# Led_Circle.net
KiCad netlist of a schematic drawn in EAGLE
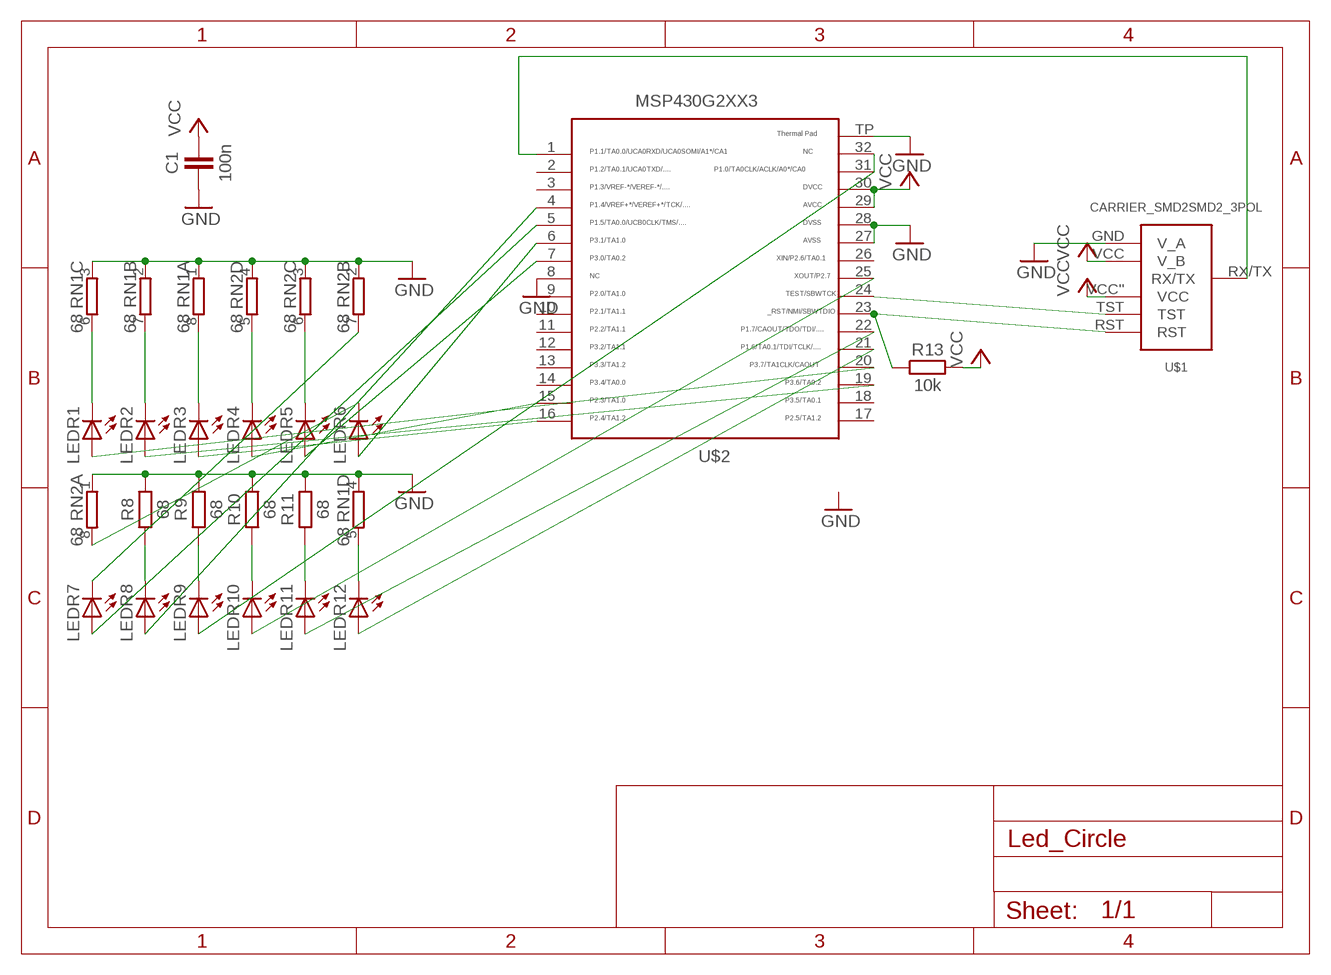
[diagram p0: schematic, sheet 1]

(export (version "E")
  (design (tool "Eeschema 10.0.6"))
  (components
    (comp (ref "C1")
      (value "100n")
      (footprint "eagle-import:603")
      (libsource (lib "eagle-import") (part "CAPACITOR"))
    )
    (comp (ref "LEDR1")
      (value "LEDCHIPLED_0603")
      (footprint "eagle-import:CHIPLED_0603")
      (libsource (lib "eagle-import") (part "LEDCHIPLED_0603"))
    )
    (comp (ref "LEDR2")
      (value "LEDCHIPLED_0603")
      (footprint "eagle-import:CHIPLED_0603")
      (libsource (lib "eagle-import") (part "LEDCHIPLED_0603"))
    )
    (comp (ref "LEDR3")
      (value "LEDCHIPLED_0603")
      (footprint "eagle-import:CHIPLED_0603")
      (libsource (lib "eagle-import") (part "LEDCHIPLED_0603"))
    )
    (comp (ref "LEDR4")
      (value "LEDCHIPLED_0603")
      (footprint "eagle-import:CHIPLED_0603")
      (libsource (lib "eagle-import") (part "LEDCHIPLED_0603"))
    )
    (comp (ref "LEDR5")
      (value "LEDCHIPLED_0603")
      (footprint "eagle-import:CHIPLED_0603")
      (libsource (lib "eagle-import") (part "LEDCHIPLED_0603"))
    )
    (comp (ref "LEDR6")
      (value "LEDCHIPLED_0603")
      (footprint "eagle-import:CHIPLED_0603")
      (libsource (lib "eagle-import") (part "LEDCHIPLED_0603"))
    )
    (comp (ref "LEDR7")
      (value "LEDCHIPLED_0603")
      (footprint "eagle-import:CHIPLED_0603")
      (libsource (lib "eagle-import") (part "LEDCHIPLED_0603"))
    )
    (comp (ref "LEDR8")
      (value "LEDCHIPLED_0603")
      (footprint "eagle-import:CHIPLED_0603")
      (libsource (lib "eagle-import") (part "LEDCHIPLED_0603"))
    )
    (comp (ref "LEDR9")
      (value "LEDCHIPLED_0603")
      (footprint "eagle-import:CHIPLED_0603")
      (libsource (lib "eagle-import") (part "LEDCHIPLED_0603"))
    )
    (comp (ref "LEDR10")
      (value "LEDCHIPLED_0603")
      (footprint "eagle-import:CHIPLED_0603")
      (libsource (lib "eagle-import") (part "LEDCHIPLED_0603"))
    )
    (comp (ref "LEDR11")
      (value "LEDCHIPLED_0603")
      (footprint "eagle-import:CHIPLED_0603")
      (libsource (lib "eagle-import") (part "LEDCHIPLED_0603"))
    )
    (comp (ref "LEDR12")
      (value "LEDCHIPLED_0603")
      (footprint "eagle-import:CHIPLED_0603")
      (libsource (lib "eagle-import") (part "LEDCHIPLED_0603"))
    )
    (comp (ref "R8")
      (value "68")
      (footprint "eagle-import:603")
      (libsource (lib "eagle-import") (part "RESISTOR0603"))
    )
    (comp (ref "R9")
      (value "68")
      (footprint "eagle-import:603")
      (libsource (lib "eagle-import") (part "RESISTOR0603"))
    )
    (comp (ref "R10")
      (value "68")
      (footprint "eagle-import:603")
      (libsource (lib "eagle-import") (part "RESISTOR0603"))
    )
    (comp (ref "R11")
      (value "68")
      (footprint "eagle-import:603")
      (libsource (lib "eagle-import") (part "RESISTOR0603"))
    )
    (comp (ref "R13")
      (value "10k")
      (footprint "eagle-import:603")
      (libsource (lib "eagle-import") (part "RESISTOR0603"))
    )
    (comp (ref "RN1")
      (value "68")
      (footprint "eagle-import:0603-ARC")
      (libsource (lib "eagle-import") (part "4R-N0603-ARC"))
    )
    (comp (ref "RN2")
      (value "68")
      (footprint "eagle-import:0603-ARC")
      (libsource (lib "eagle-import") (part "4R-N0603-ARC"))
    )
    (comp (ref "U$1")
      (value "CARRIER_SMD2SMD2_3POL")
      (footprint "eagle-import:CARRIER_SMD2_3POL")
      (libsource (lib "eagle-import") (part "CARRIER_SMD2SMD2_3POL"))
    )
    (comp (ref "U$2")
      (value "MSP430G2553")
      (footprint "eagle-import:QFN32")
      (libsource (lib "eagle-import") (part "MSP430G2553"))
    )
  )
  (nets
    (net (code "1") (name "GND") (class "Default")
      (node (ref "C1") (pin "1") (pinfunction "1_1") (pintype "passive"))
      (node (ref "R10") (pin "2") (pinfunction "2_2") (pintype "passive"))
      (node (ref "R11") (pin "2") (pinfunction "2_2") (pintype "passive"))
      (node (ref "R8") (pin "2") (pinfunction "2_2") (pintype "passive"))
      (node (ref "R9") (pin "2") (pinfunction "2_2") (pintype "passive"))
      (node (ref "RN1") (pin "1") (pinfunction "1_1") (pintype "passive"))
      (node (ref "RN1") (pin "2") (pinfunction "1_2") (pintype "passive"))
      (node (ref "RN1") (pin "3") (pinfunction "1_3") (pintype "passive"))
      (node (ref "RN1") (pin "4") (pinfunction "1_4") (pintype "passive"))
      (node (ref "RN2") (pin "1") (pinfunction "1_1") (pintype "passive"))
      (node (ref "RN2") (pin "2") (pinfunction "1_2") (pintype "passive"))
      (node (ref "RN2") (pin "3") (pinfunction "1_3") (pintype "passive"))
      (node (ref "RN2") (pin "4") (pinfunction "1_4") (pintype "passive"))
      (node (ref "U$1") (pin "GND") (pinfunction "V_A_GND") (pintype "bidirectional"))
      (node (ref "U$2") (pin "27") (pinfunction "27_27") (pintype "bidirectional"))
      (node (ref "U$2") (pin "28") (pinfunction "28_28") (pintype "bidirectional"))
      (node (ref "U$2") (pin "8") (pinfunction "8_8") (pintype "bidirectional"))
      (node (ref "U$2") (pin "TP") (pinfunction "TP_TP") (pintype "bidirectional"))
    )
    (net (code "2") (name "Net-(LEDR1-PadA)") (class "Default")
      (node (ref "LEDR1") (pin "A") (pinfunction "A_A") (pintype "passive"))
      (node (ref "U$2") (pin "20") (pinfunction "20_20") (pintype "bidirectional"))
    )
    (net (code "3") (name "Net-(LEDR2-PadA)") (class "Default")
      (node (ref "LEDR2") (pin "A") (pinfunction "A_A") (pintype "passive"))
      (node (ref "U$2") (pin "19") (pinfunction "19_19") (pintype "bidirectional"))
    )
    (net (code "4") (name "Net-(LEDR3-PadA)") (class "Default")
      (node (ref "LEDR3") (pin "A") (pinfunction "A_A") (pintype "passive"))
      (node (ref "U$2") (pin "16") (pinfunction "16_16") (pintype "bidirectional"))
    )
    (net (code "5") (name "Net-(LEDR4-PadA)") (class "Default")
      (node (ref "LEDR4") (pin "A") (pinfunction "A_A") (pintype "passive"))
      (node (ref "U$2") (pin "15") (pinfunction "15_15") (pintype "bidirectional"))
    )
    (net (code "6") (name "Net-(LEDR5-PadA)") (class "Default")
      (node (ref "LEDR5") (pin "A") (pinfunction "A_A") (pintype "passive"))
      (node (ref "U$2") (pin "7") (pinfunction "7_7") (pintype "bidirectional"))
    )
    (net (code "7") (name "Net-(LEDR6-PadA)") (class "Default")
      (node (ref "LEDR6") (pin "A") (pinfunction "A_A") (pintype "passive"))
      (node (ref "U$2") (pin "6") (pinfunction "6_6") (pintype "bidirectional"))
    )
    (net (code "8") (name "Net-(LEDR7-PadA)") (class "Default")
      (node (ref "LEDR7") (pin "A") (pinfunction "A_A") (pintype "passive"))
      (node (ref "U$2") (pin "5") (pinfunction "5_5") (pintype "bidirectional"))
    )
    (net (code "9") (name "Net-(LEDR8-PadA)") (class "Default")
      (node (ref "LEDR8") (pin "A") (pinfunction "A_A") (pintype "passive"))
      (node (ref "U$2") (pin "4") (pinfunction "4_4") (pintype "bidirectional"))
    )
    (net (code "10") (name "Net-(LEDR8-PadC)") (class "Default")
      (node (ref "LEDR8") (pin "C") (pinfunction "C_C") (pintype "passive"))
      (node (ref "R8") (pin "1") (pinfunction "1_1") (pintype "passive"))
    )
    (net (code "11") (name "Net-(LEDR9-PadA)") (class "Default")
      (node (ref "LEDR9") (pin "A") (pinfunction "A_A") (pintype "passive"))
      (node (ref "U$2") (pin "31") (pinfunction "31_31") (pintype "bidirectional"))
      (node (ref "U$2") (pin "32") (pinfunction "32_32") (pintype "bidirectional"))
    )
    (net (code "12") (name "Net-(LEDR9-PadC)") (class "Default")
      (node (ref "LEDR9") (pin "C") (pinfunction "C_C") (pintype "passive"))
      (node (ref "R9") (pin "1") (pinfunction "1_1") (pintype "passive"))
    )
    (net (code "13") (name "Net-(LEDR10-PadA)") (class "Default")
      (node (ref "LEDR10") (pin "A") (pinfunction "A_A") (pintype "passive"))
      (node (ref "U$2") (pin "25") (pinfunction "25_25") (pintype "bidirectional"))
    )
    (net (code "14") (name "Net-(LEDR10-PadC)") (class "Default")
      (node (ref "LEDR10") (pin "C") (pinfunction "C_C") (pintype "passive"))
      (node (ref "R10") (pin "1") (pinfunction "1_1") (pintype "passive"))
    )
    (net (code "15") (name "Net-(LEDR11-PadA)") (class "Default")
      (node (ref "LEDR11") (pin "A") (pinfunction "A_A") (pintype "passive"))
      (node (ref "U$2") (pin "22") (pinfunction "22_22") (pintype "bidirectional"))
    )
    (net (code "16") (name "Net-(LEDR11-PadC)") (class "Default")
      (node (ref "LEDR11") (pin "C") (pinfunction "C_C") (pintype "passive"))
      (node (ref "R11") (pin "1") (pinfunction "1_1") (pintype "passive"))
    )
    (net (code "17") (name "Net-(LEDR12-PadA)") (class "Default")
      (node (ref "LEDR12") (pin "A") (pinfunction "A_A") (pintype "passive"))
      (node (ref "U$2") (pin "21") (pinfunction "21_21") (pintype "bidirectional"))
    )
    (net (code "18") (name "Net-(R13-Pad1)") (class "Default")
      (node (ref "R13") (pin "1") (pinfunction "1_1") (pintype "passive"))
      (node (ref "U$1") (pin "RST") (pinfunction "RST_RST") (pintype "bidirectional"))
      (node (ref "U$2") (pin "23") (pinfunction "23_23") (pintype "bidirectional"))
    )
    (net (code "19") (name "Net-(RN1A-2)") (class "Default")
      (node (ref "LEDR3") (pin "C") (pinfunction "C_C") (pintype "passive"))
      (node (ref "RN1") (pin "8") (pinfunction "2_8") (pintype "passive"))
    )
    (net (code "20") (name "Net-(RN1B-2)") (class "Default")
      (node (ref "LEDR2") (pin "C") (pinfunction "C_C") (pintype "passive"))
      (node (ref "RN1") (pin "7") (pinfunction "2_7") (pintype "passive"))
    )
    (net (code "21") (name "Net-(RN1C-2)") (class "Default")
      (node (ref "LEDR1") (pin "C") (pinfunction "C_C") (pintype "passive"))
      (node (ref "RN1") (pin "6") (pinfunction "2_6") (pintype "passive"))
    )
    (net (code "22") (name "Net-(RN1D-2)") (class "Default")
      (node (ref "LEDR12") (pin "C") (pinfunction "C_C") (pintype "passive"))
      (node (ref "RN1") (pin "5") (pinfunction "2_5") (pintype "passive"))
    )
    (net (code "23") (name "Net-(RN2A-2)") (class "Default")
      (node (ref "LEDR6") (pin "C") (pinfunction "C_C") (pintype "passive"))
      (node (ref "RN2") (pin "8") (pinfunction "2_8") (pintype "passive"))
    )
    (net (code "24") (name "Net-(RN2B-2)") (class "Default")
      (node (ref "LEDR7") (pin "C") (pinfunction "C_C") (pintype "passive"))
      (node (ref "RN2") (pin "7") (pinfunction "2_7") (pintype "passive"))
    )
    (net (code "25") (name "Net-(RN2C-2)") (class "Default")
      (node (ref "LEDR5") (pin "C") (pinfunction "C_C") (pintype "passive"))
      (node (ref "RN2") (pin "6") (pinfunction "2_6") (pintype "passive"))
    )
    (net (code "26") (name "Net-(RN2D-2)") (class "Default")
      (node (ref "LEDR4") (pin "C") (pinfunction "C_C") (pintype "passive"))
      (node (ref "RN2") (pin "5") (pinfunction "2_5") (pintype "passive"))
    )
    (net (code "27") (name "Net-(U$1-PadRX{slash}TX)") (class "Default")
      (node (ref "U$1") (pin "RX/TX") (pinfunction "RX/TX_RX/TX") (pintype "bidirectional"))
      (node (ref "U$2") (pin "1") (pinfunction "1_1") (pintype "bidirectional"))
    )
    (net (code "28") (name "Net-(U$1-PadTST)") (class "Default")
      (node (ref "U$1") (pin "TST") (pinfunction "TST_TST") (pintype "bidirectional"))
      (node (ref "U$2") (pin "24") (pinfunction "24_24") (pintype "bidirectional"))
    )
    (net (code "29") (name "VCC") (class "Default")
      (node (ref "C1") (pin "2") (pinfunction "2_2") (pintype "passive"))
      (node (ref "R13") (pin "2") (pinfunction "2_2") (pintype "passive"))
      (node (ref "U$1") (pin "VCC") (pinfunction "V_B_VCC") (pintype "bidirectional"))
      (node (ref "U$1") (pin "VCC''") (pinfunction "VCC_VCC''") (pintype "bidirectional"))
      (node (ref "U$2") (pin "29") (pinfunction "29_29") (pintype "bidirectional"))
      (node (ref "U$2") (pin "30") (pinfunction "30_30") (pintype "bidirectional"))
    )
    (net (code "30") (name "unconnected-(U$2-Pad2)") (class "Default")
      (node (ref "U$2") (pin "2") (pinfunction "2_2") (pintype "bidirectional"))
    )
    (net (code "31") (name "unconnected-(U$2-Pad3)") (class "Default")
      (node (ref "U$2") (pin "3") (pinfunction "3_3") (pintype "bidirectional"))
    )
    (net (code "32") (name "unconnected-(U$2-Pad9)") (class "Default")
      (node (ref "U$2") (pin "9") (pinfunction "9_9") (pintype "bidirectional"))
    )
    (net (code "33") (name "unconnected-(U$2-Pad10)") (class "Default")
      (node (ref "U$2") (pin "10") (pinfunction "10_10") (pintype "bidirectional"))
    )
    (net (code "34") (name "unconnected-(U$2-Pad11)") (class "Default")
      (node (ref "U$2") (pin "11") (pinfunction "11_11") (pintype "bidirectional"))
    )
    (net (code "35") (name "unconnected-(U$2-Pad12)") (class "Default")
      (node (ref "U$2") (pin "12") (pinfunction "12_12") (pintype "bidirectional"))
    )
    (net (code "36") (name "unconnected-(U$2-Pad13)") (class "Default")
      (node (ref "U$2") (pin "13") (pinfunction "13_13") (pintype "bidirectional"))
    )
    (net (code "37") (name "unconnected-(U$2-Pad14)") (class "Default")
      (node (ref "U$2") (pin "14") (pinfunction "14_14") (pintype "bidirectional"))
    )
    (net (code "38") (name "unconnected-(U$2-Pad17)") (class "Default")
      (node (ref "U$2") (pin "17") (pinfunction "17_17") (pintype "bidirectional"))
    )
    (net (code "39") (name "unconnected-(U$2-Pad18)") (class "Default")
      (node (ref "U$2") (pin "18") (pinfunction "18_18") (pintype "bidirectional"))
    )
    (net (code "40") (name "unconnected-(U$2-Pad26)") (class "Default")
      (node (ref "U$2") (pin "26") (pinfunction "26_26") (pintype "bidirectional"))
    )
  )
)
